# USBCastel.net
KiCad netlist of a schematic drawn in EAGLE
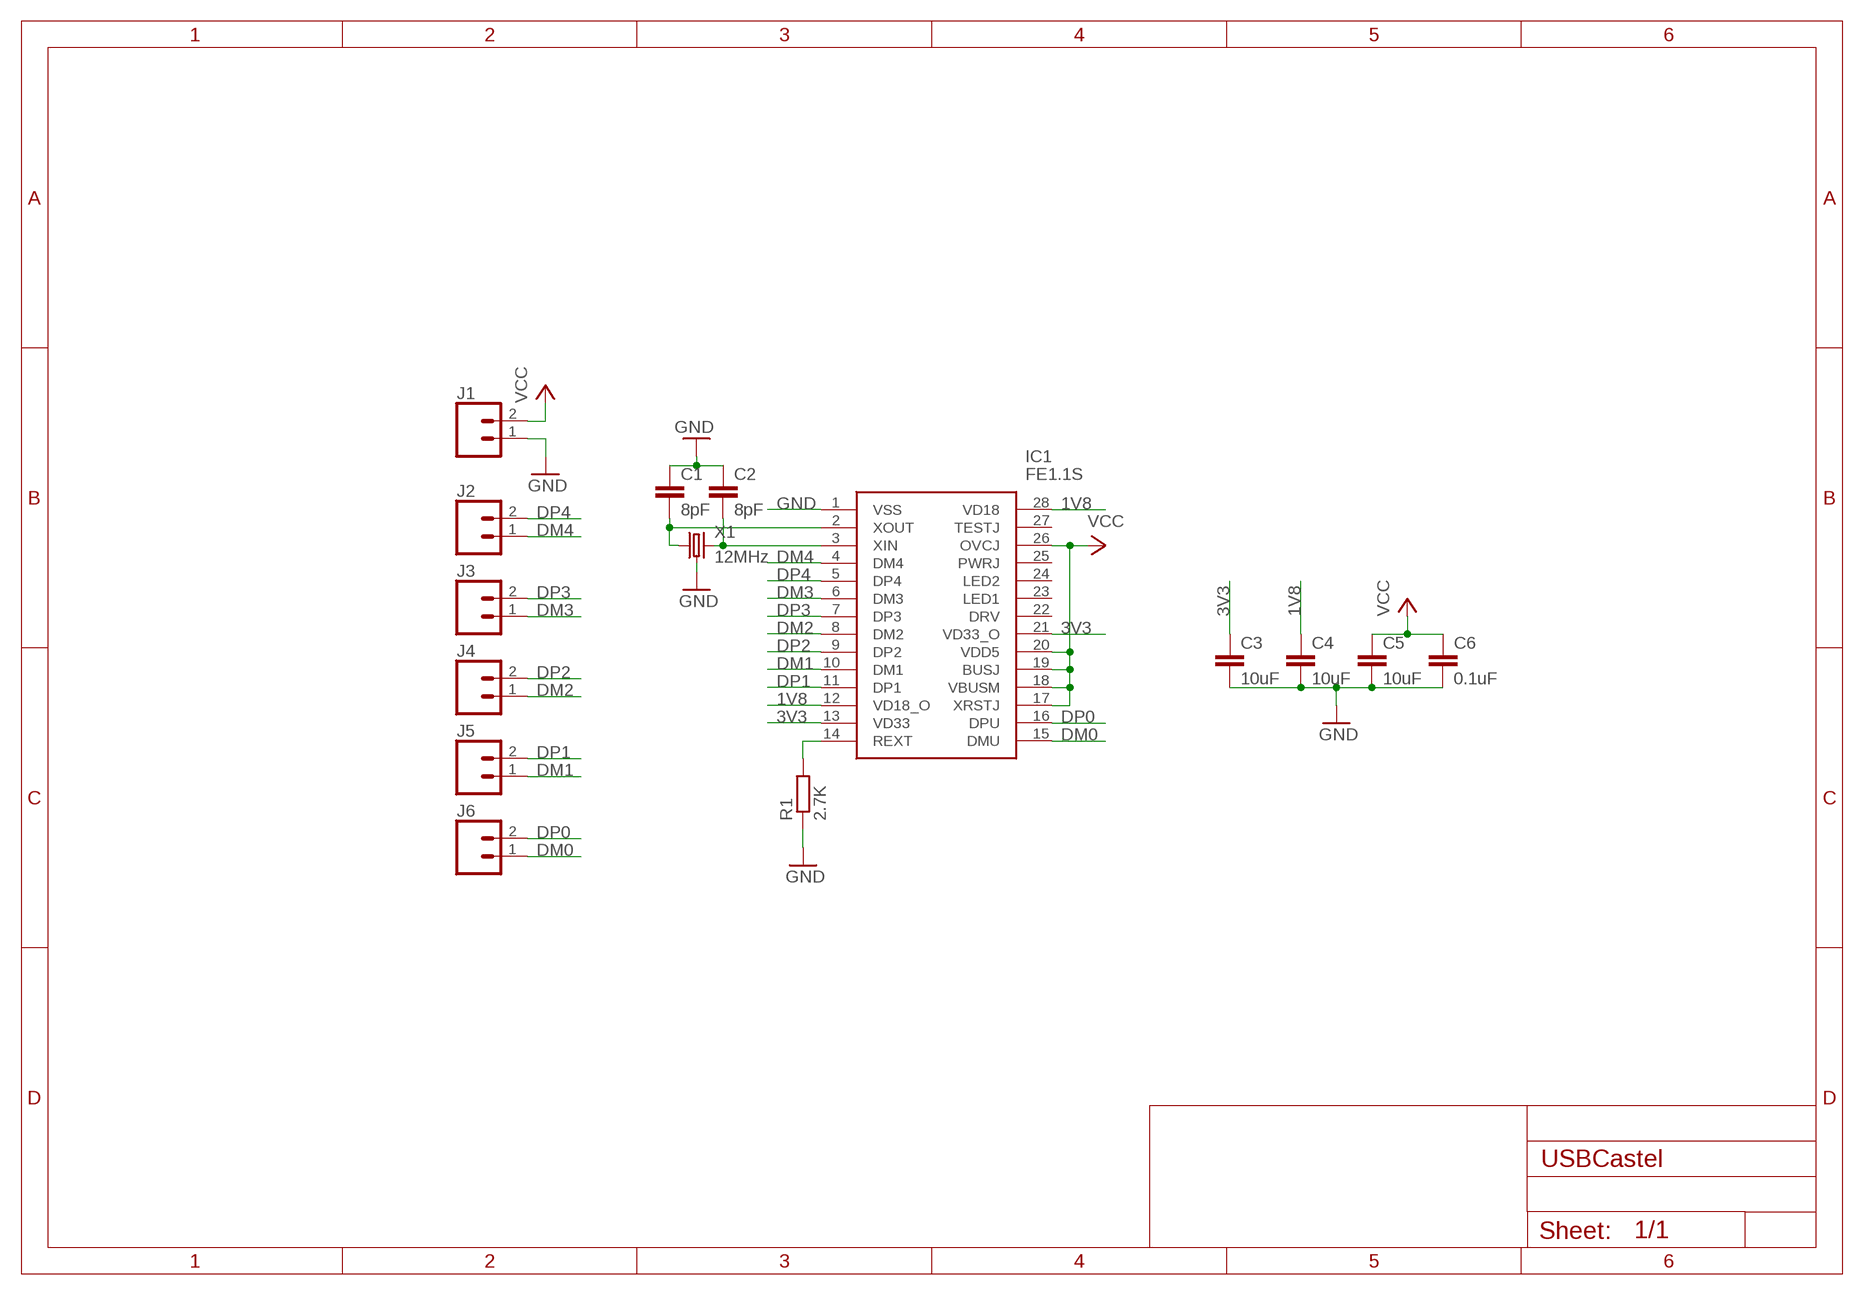
[diagram p0: schematic, sheet 1]

(export (version "E")
  (design (tool "Eeschema 10.0.6"))
  (components
    (comp (ref "C1")
      (value "8pF")
      (footprint "eagle-import:C0402")
      (libsource (lib "eagle-import") (part "C-EUC0402"))
    )
    (comp (ref "C2")
      (value "8pF")
      (footprint "eagle-import:C0402")
      (libsource (lib "eagle-import") (part "C-EUC0402"))
    )
    (comp (ref "C3")
      (value "10uF")
      (footprint "eagle-import:C0402")
      (libsource (lib "eagle-import") (part "C-EUC0402"))
    )
    (comp (ref "C4")
      (value "10uF")
      (footprint "eagle-import:C0402")
      (libsource (lib "eagle-import") (part "C-EUC0402"))
    )
    (comp (ref "C5")
      (value "10uF")
      (footprint "eagle-import:C0402")
      (libsource (lib "eagle-import") (part "C-EUC0402"))
    )
    (comp (ref "C6")
      (value "0.1uF")
      (footprint "eagle-import:C0402")
      (libsource (lib "eagle-import") (part "C-EUC0402"))
    )
    (comp (ref "IC1")
      (value "FE1.1S")
      (footprint "eagle-import:SOP64P600X175-28N")
      (libsource (lib "eagle-import") (part "FE1.1S"))
    )
    (comp (ref "J1")
      (value "CONN_021X02_NO_SILK")
      (footprint "eagle-import:1X02_NO_SILK")
      (libsource (lib "eagle-import") (part "CONN_021X02_NO_SILK"))
    )
    (comp (ref "J2")
      (value "CONN_021X02_NO_SILK")
      (footprint "eagle-import:1X02_NO_SILK")
      (libsource (lib "eagle-import") (part "CONN_021X02_NO_SILK"))
    )
    (comp (ref "J3")
      (value "CONN_021X02_NO_SILK")
      (footprint "eagle-import:1X02_NO_SILK")
      (libsource (lib "eagle-import") (part "CONN_021X02_NO_SILK"))
    )
    (comp (ref "J4")
      (value "CONN_021X02_NO_SILK")
      (footprint "eagle-import:1X02_NO_SILK")
      (libsource (lib "eagle-import") (part "CONN_021X02_NO_SILK"))
    )
    (comp (ref "J5")
      (value "CONN_021X02_NO_SILK")
      (footprint "eagle-import:1X02_NO_SILK")
      (libsource (lib "eagle-import") (part "CONN_021X02_NO_SILK"))
    )
    (comp (ref "J6")
      (value "CONN_021X02_NO_SILK")
      (footprint "eagle-import:1X02_NO_SILK")
      (libsource (lib "eagle-import") (part "CONN_021X02_NO_SILK"))
    )
    (comp (ref "R1")
      (value "2.7K")
      (footprint "eagle-import:R0402")
      (libsource (lib "eagle-import") (part "R-EU_R0402"))
    )
    (comp (ref "X1")
      (value "12MHz")
      (footprint "eagle-import:ABM10")
      (libsource (lib "eagle-import") (part "ABM10"))
    )
  )
  (nets
    (net (code "1") (name "/1V8") (class "Default")
      (node (ref "C4") (pin "1") (pinfunction "1_1") (pintype "passive"))
      (node (ref "IC1") (pin "12") (pinfunction "VD18_O_12") (pintype "bidirectional"))
      (node (ref "IC1") (pin "28") (pinfunction "VD18_28") (pintype "bidirectional"))
    )
    (net (code "2") (name "/3V3") (class "Default")
      (node (ref "C3") (pin "1") (pinfunction "1_1") (pintype "passive"))
      (node (ref "IC1") (pin "13") (pinfunction "VD33_13") (pintype "bidirectional"))
      (node (ref "IC1") (pin "21") (pinfunction "VD33_O_21") (pintype "bidirectional"))
    )
    (net (code "3") (name "/DM0") (class "Default")
      (node (ref "IC1") (pin "15") (pinfunction "DMU_15") (pintype "bidirectional"))
      (node (ref "J6") (pin "1") (pinfunction "1_1") (pintype "passive"))
    )
    (net (code "4") (name "/DM1") (class "Default")
      (node (ref "IC1") (pin "10") (pinfunction "DM1_10") (pintype "bidirectional"))
      (node (ref "J5") (pin "1") (pinfunction "1_1") (pintype "passive"))
    )
    (net (code "5") (name "/DM2") (class "Default")
      (node (ref "IC1") (pin "8") (pinfunction "DM2_8") (pintype "bidirectional"))
      (node (ref "J4") (pin "1") (pinfunction "1_1") (pintype "passive"))
    )
    (net (code "6") (name "/DM3") (class "Default")
      (node (ref "IC1") (pin "6") (pinfunction "DM3_6") (pintype "bidirectional"))
      (node (ref "J3") (pin "1") (pinfunction "1_1") (pintype "passive"))
    )
    (net (code "7") (name "/DM4") (class "Default")
      (node (ref "IC1") (pin "4") (pinfunction "DM4_4") (pintype "bidirectional"))
      (node (ref "J2") (pin "1") (pinfunction "1_1") (pintype "passive"))
    )
    (net (code "8") (name "/DP0") (class "Default")
      (node (ref "IC1") (pin "16") (pinfunction "DPU_16") (pintype "bidirectional"))
      (node (ref "J6") (pin "2") (pinfunction "2_2") (pintype "passive"))
    )
    (net (code "9") (name "/DP1") (class "Default")
      (node (ref "IC1") (pin "11") (pinfunction "DP1_11") (pintype "bidirectional"))
      (node (ref "J5") (pin "2") (pinfunction "2_2") (pintype "passive"))
    )
    (net (code "10") (name "/DP2") (class "Default")
      (node (ref "IC1") (pin "9") (pinfunction "DP2_9") (pintype "bidirectional"))
      (node (ref "J4") (pin "2") (pinfunction "2_2") (pintype "passive"))
    )
    (net (code "11") (name "/DP3") (class "Default")
      (node (ref "IC1") (pin "7") (pinfunction "DP3_7") (pintype "bidirectional"))
      (node (ref "J3") (pin "2") (pinfunction "2_2") (pintype "passive"))
    )
    (net (code "12") (name "/DP4") (class "Default")
      (node (ref "IC1") (pin "5") (pinfunction "DP4_5") (pintype "bidirectional"))
      (node (ref "J2") (pin "2") (pinfunction "2_2") (pintype "passive"))
    )
    (net (code "13") (name "GND") (class "Default")
      (node (ref "C1") (pin "1") (pinfunction "1_1") (pintype "passive"))
      (node (ref "C2") (pin "1") (pinfunction "1_1") (pintype "passive"))
      (node (ref "C3") (pin "2") (pinfunction "2_2") (pintype "passive"))
      (node (ref "C4") (pin "2") (pinfunction "2_2") (pintype "passive"))
      (node (ref "C5") (pin "2") (pinfunction "2_2") (pintype "passive"))
      (node (ref "C6") (pin "2") (pinfunction "2_2") (pintype "passive"))
      (node (ref "IC1") (pin "1") (pinfunction "VSS_1") (pintype "bidirectional"))
      (node (ref "J1") (pin "1") (pinfunction "1_1") (pintype "passive"))
      (node (ref "R1") (pin "1") (pinfunction "1_1") (pintype "passive"))
      (node (ref "X1") (pin "2") (pinfunction "3_2") (pintype "bidirectional"))
      (node (ref "X1") (pin "4") (pinfunction "3_4") (pintype "bidirectional"))
    )
    (net (code "14") (name "Net-(IC1-REXT)") (class "Default")
      (node (ref "IC1") (pin "14") (pinfunction "REXT_14") (pintype "bidirectional"))
      (node (ref "R1") (pin "2") (pinfunction "2_2") (pintype "passive"))
    )
    (net (code "15") (name "Net-(IC1-XIN)") (class "Default")
      (node (ref "C2") (pin "2") (pinfunction "2_2") (pintype "passive"))
      (node (ref "IC1") (pin "3") (pinfunction "XIN_3") (pintype "bidirectional"))
      (node (ref "X1") (pin "3") (pinfunction "2_3") (pintype "passive"))
    )
    (net (code "16") (name "Net-(IC1-XOUT)") (class "Default")
      (node (ref "C1") (pin "2") (pinfunction "2_2") (pintype "passive"))
      (node (ref "IC1") (pin "2") (pinfunction "XOUT_2") (pintype "bidirectional"))
      (node (ref "X1") (pin "1") (pinfunction "1_1") (pintype "passive"))
    )
    (net (code "17") (name "VCC") (class "Default")
      (node (ref "C5") (pin "1") (pinfunction "1_1") (pintype "passive"))
      (node (ref "C6") (pin "1") (pinfunction "1_1") (pintype "passive"))
      (node (ref "IC1") (pin "17") (pinfunction "XRSTJ_17") (pintype "bidirectional"))
      (node (ref "IC1") (pin "18") (pinfunction "VBUSM_18") (pintype "bidirectional"))
      (node (ref "IC1") (pin "19") (pinfunction "BUSJ_19") (pintype "bidirectional"))
      (node (ref "IC1") (pin "20") (pinfunction "VDD5_20") (pintype "bidirectional"))
      (node (ref "IC1") (pin "26") (pinfunction "OVCJ_26") (pintype "bidirectional"))
      (node (ref "J1") (pin "2") (pinfunction "2_2") (pintype "passive"))
    )
    (net (code "18") (name "unconnected-(IC1-DRV-Pad22)") (class "Default")
      (node (ref "IC1") (pin "22") (pinfunction "DRV_22") (pintype "bidirectional"))
    )
    (net (code "19") (name "unconnected-(IC1-LED1-Pad23)") (class "Default")
      (node (ref "IC1") (pin "23") (pinfunction "LED1_23") (pintype "bidirectional"))
    )
    (net (code "20") (name "unconnected-(IC1-LED2-Pad24)") (class "Default")
      (node (ref "IC1") (pin "24") (pinfunction "LED2_24") (pintype "bidirectional"))
    )
    (net (code "21") (name "unconnected-(IC1-PWRJ-Pad25)") (class "Default")
      (node (ref "IC1") (pin "25") (pinfunction "PWRJ_25") (pintype "bidirectional"))
    )
    (net (code "22") (name "unconnected-(IC1-TESTJ-Pad27)") (class "Default")
      (node (ref "IC1") (pin "27") (pinfunction "TESTJ_27") (pintype "bidirectional"))
    )
  )
)
